# mbed-WiFi-BLE-Cloud-v1_2_0.net
KiCad netlist of a schematic drawn in EAGLE
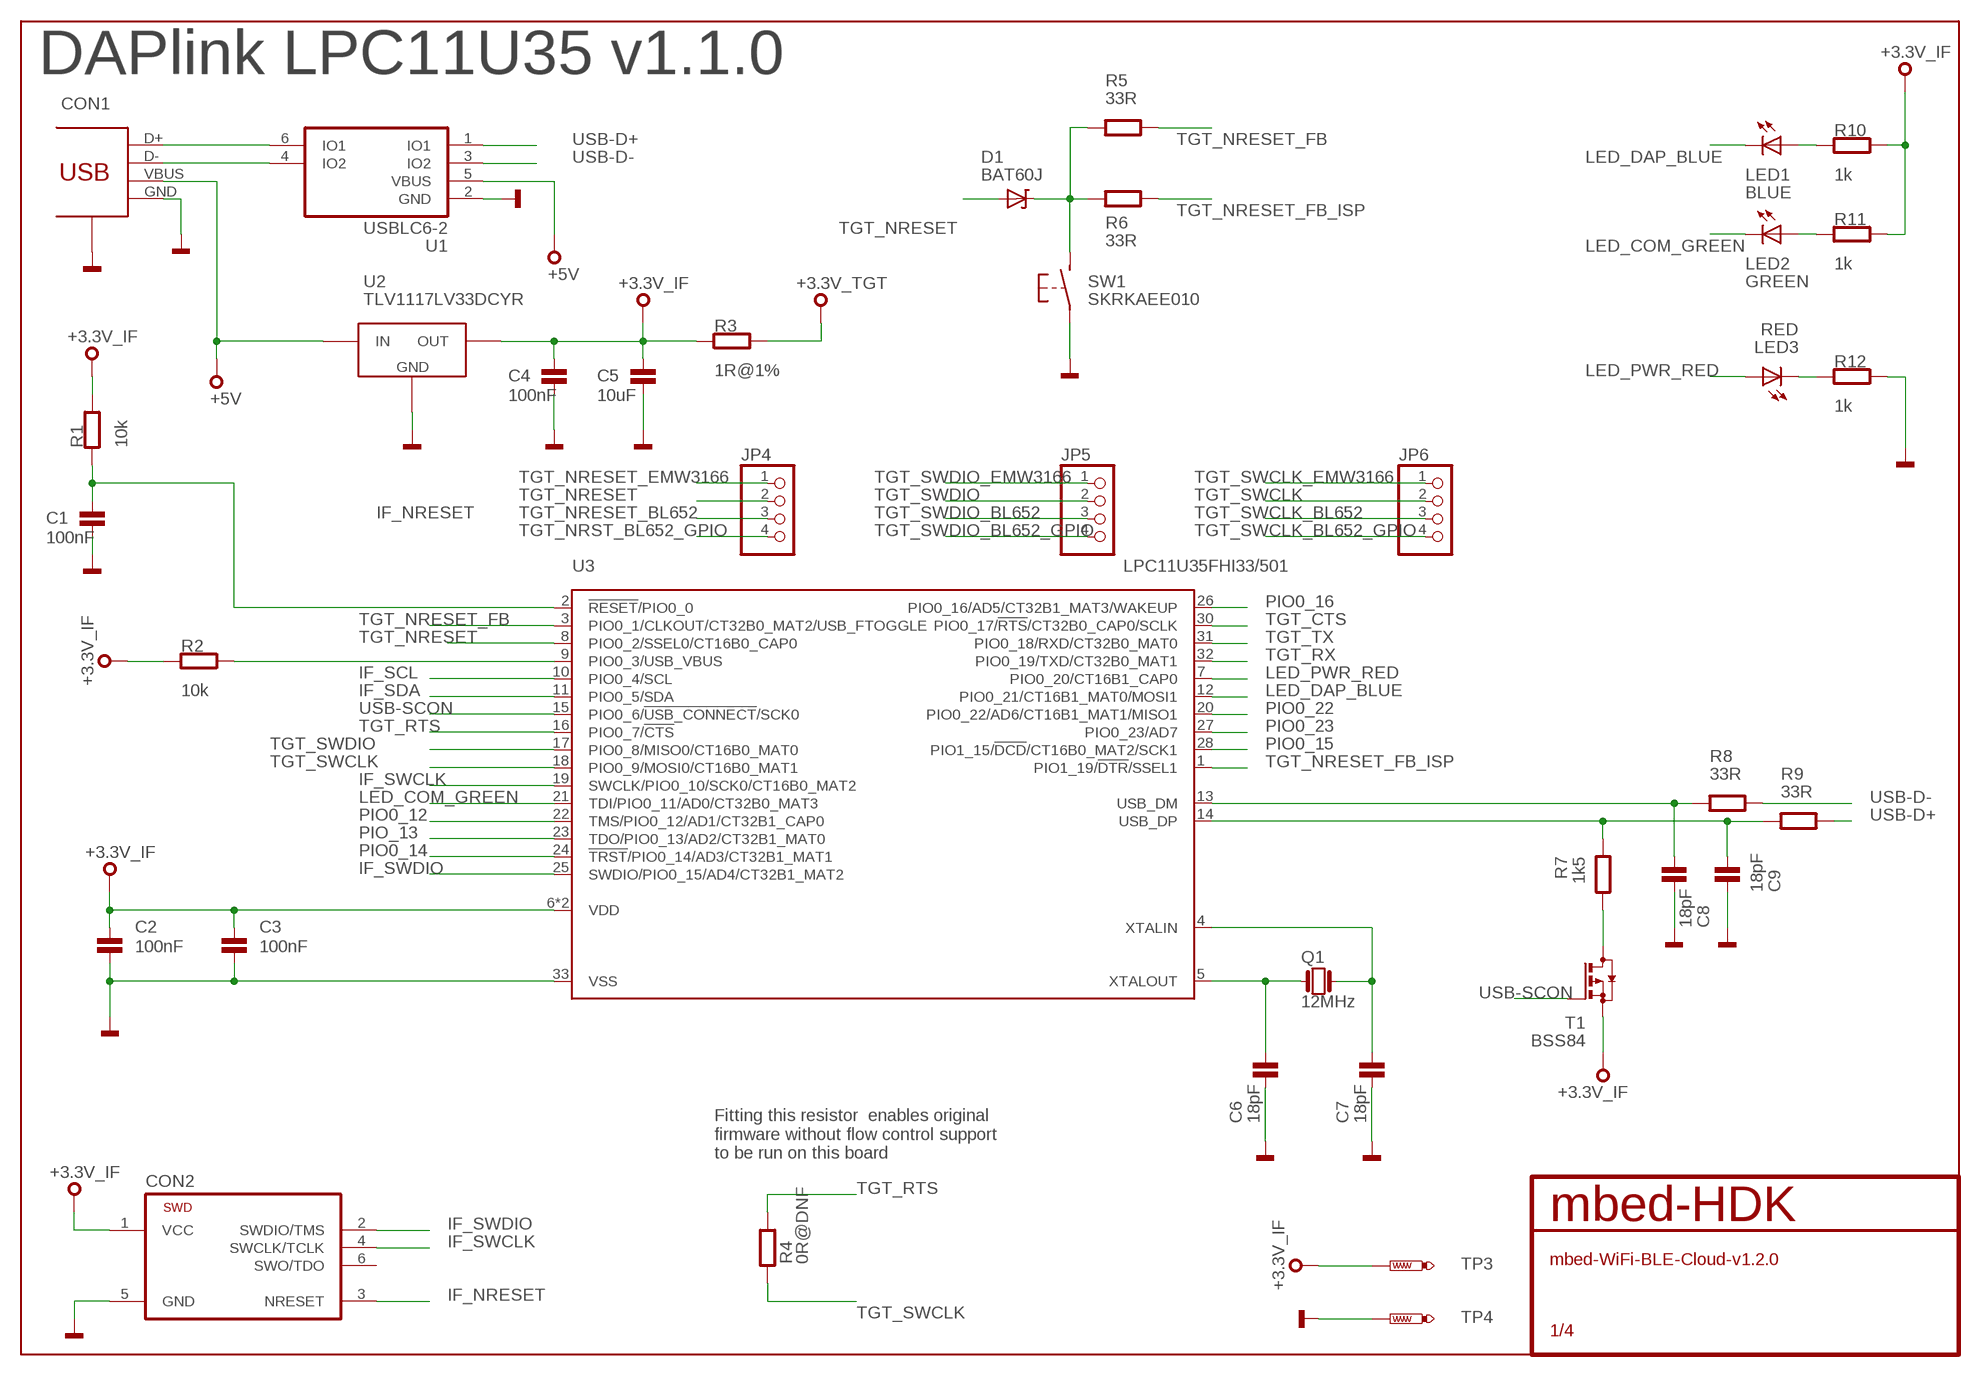
[diagram p0: schematic, sheet 1]
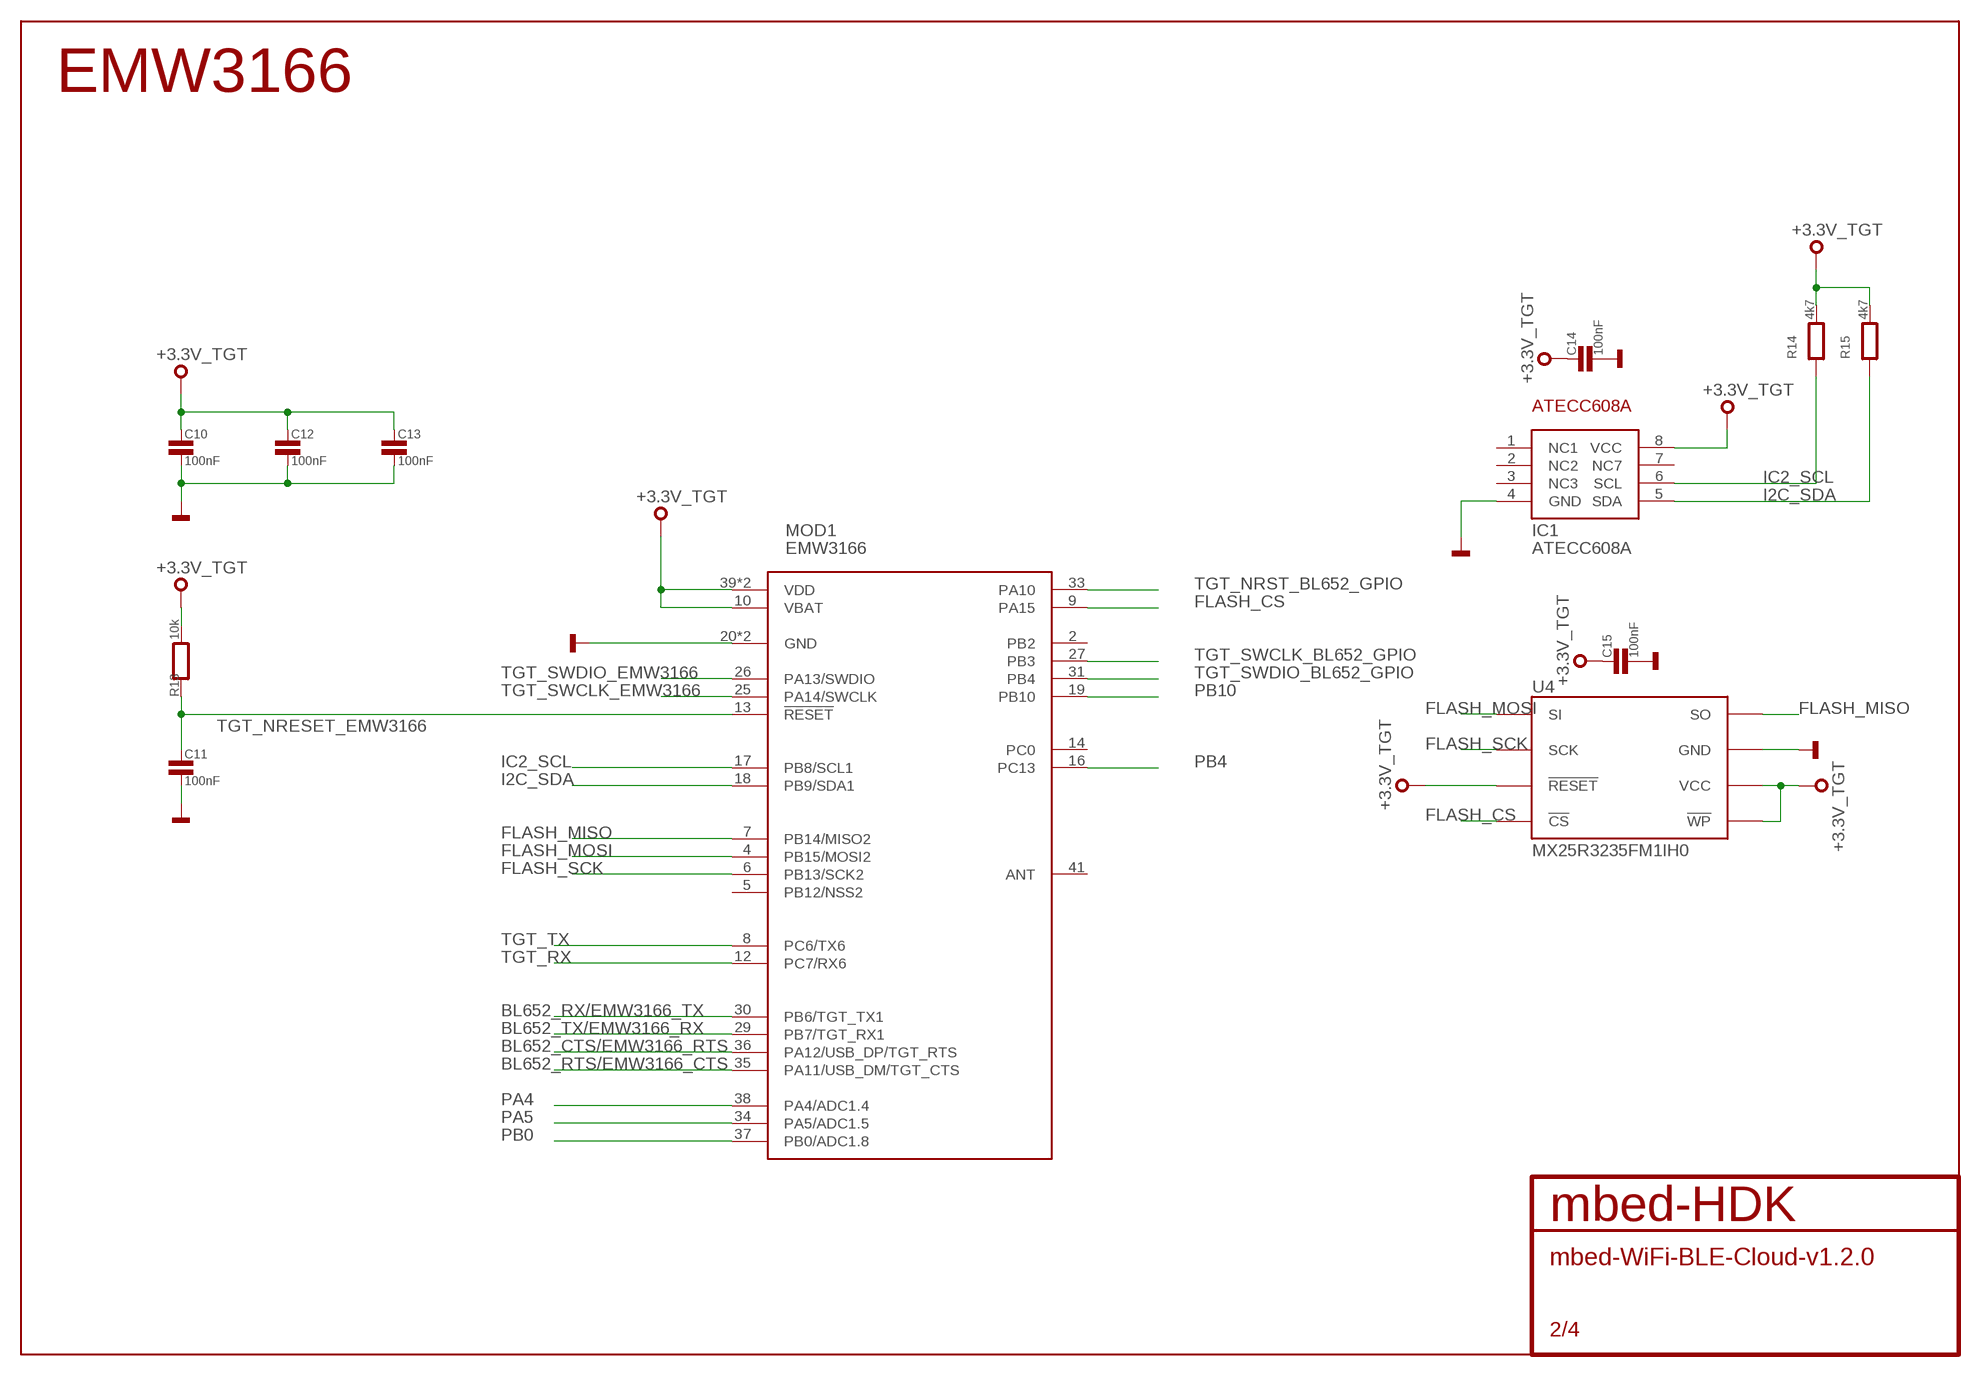
[diagram p1: schematic, sheet 2]
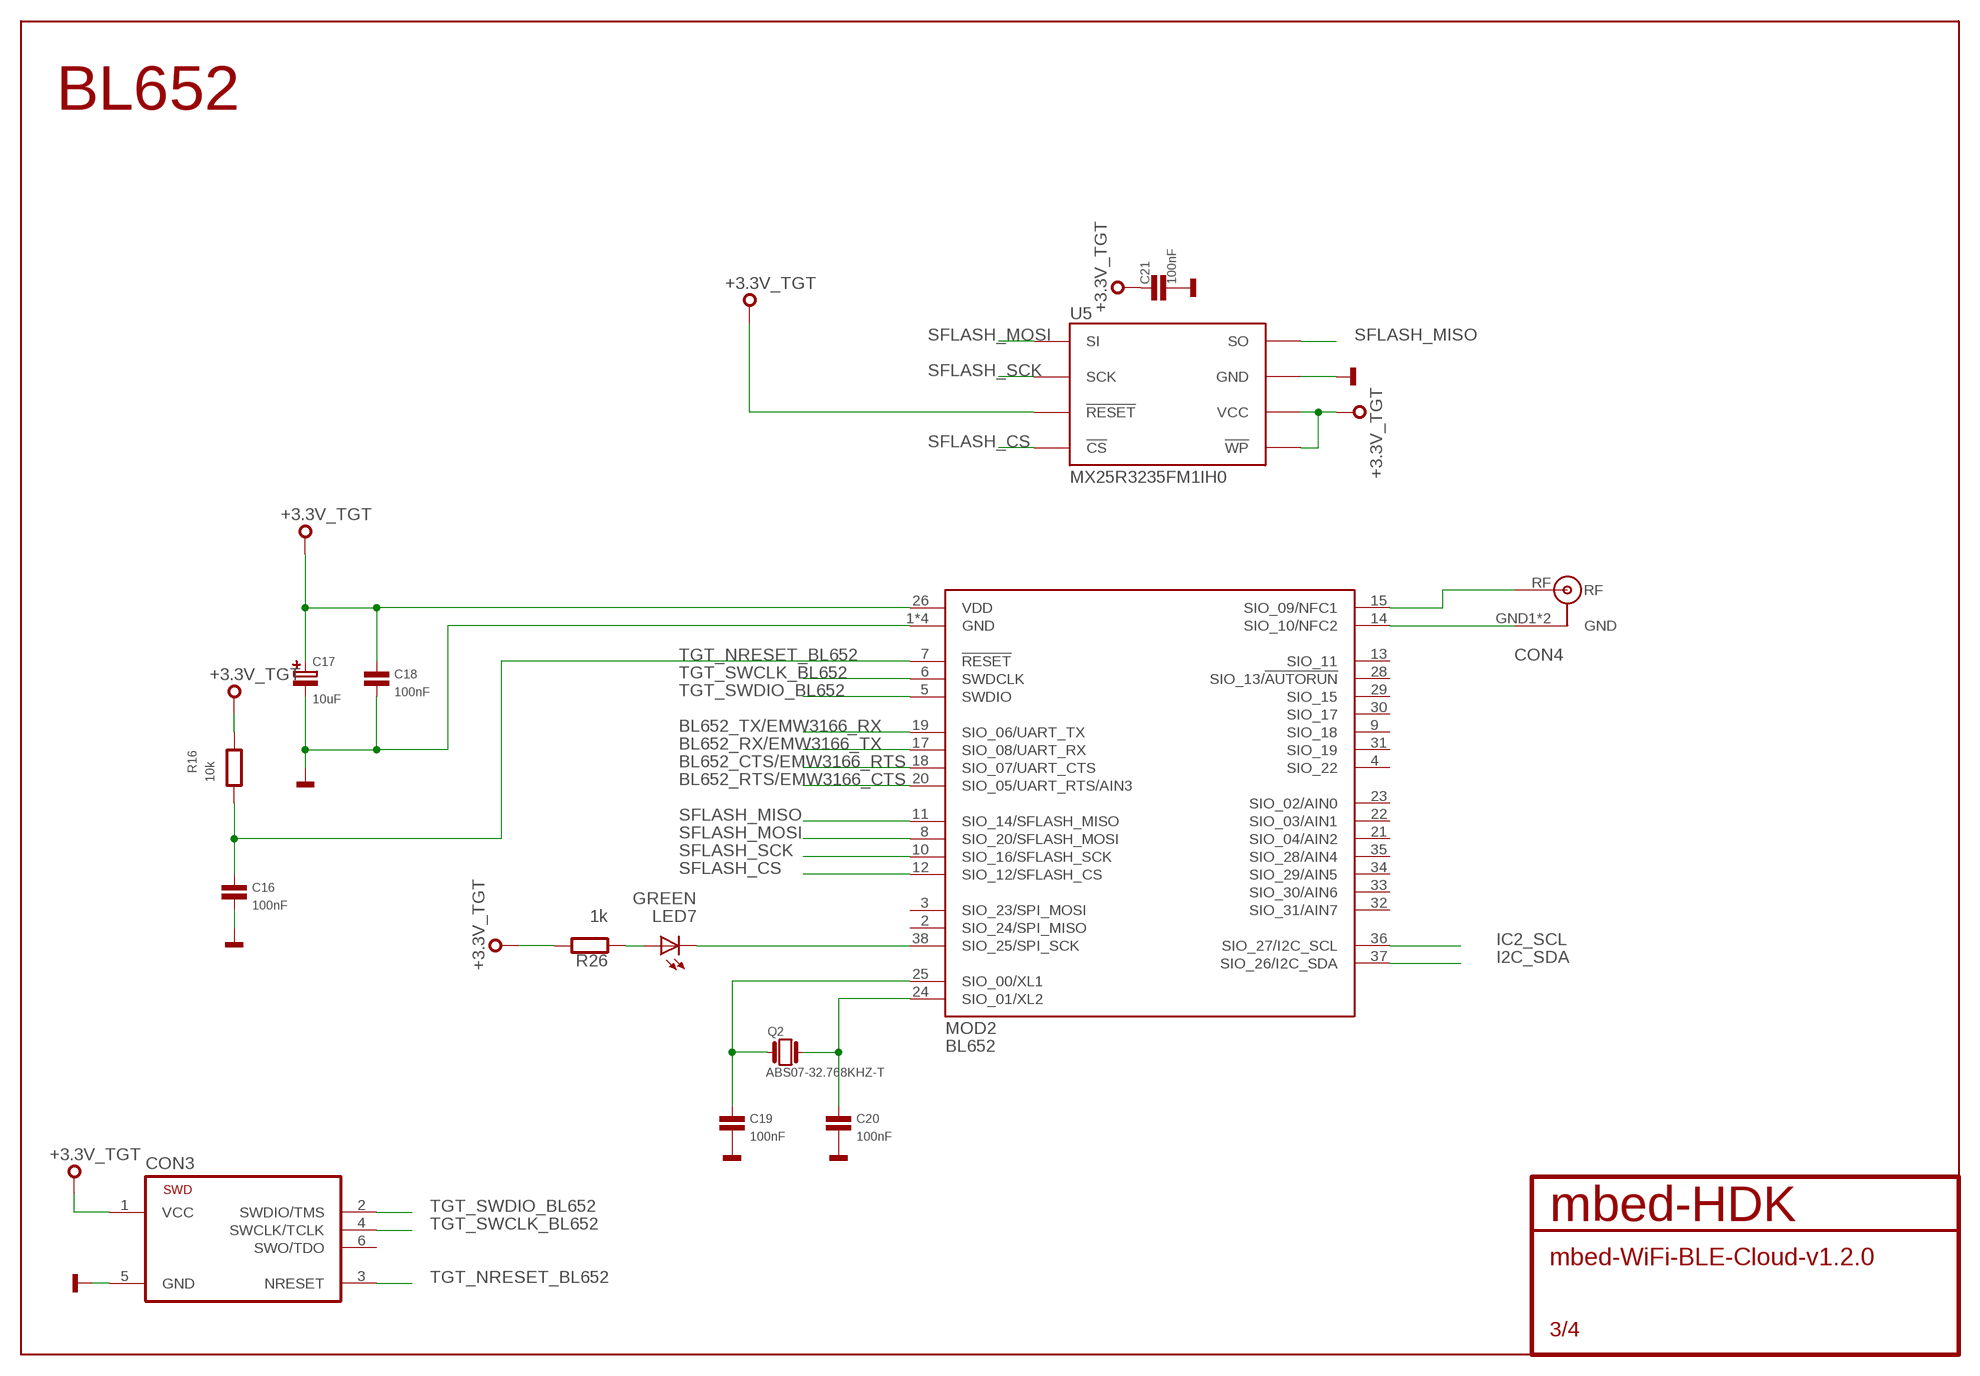
[diagram p2: schematic, sheet 3]
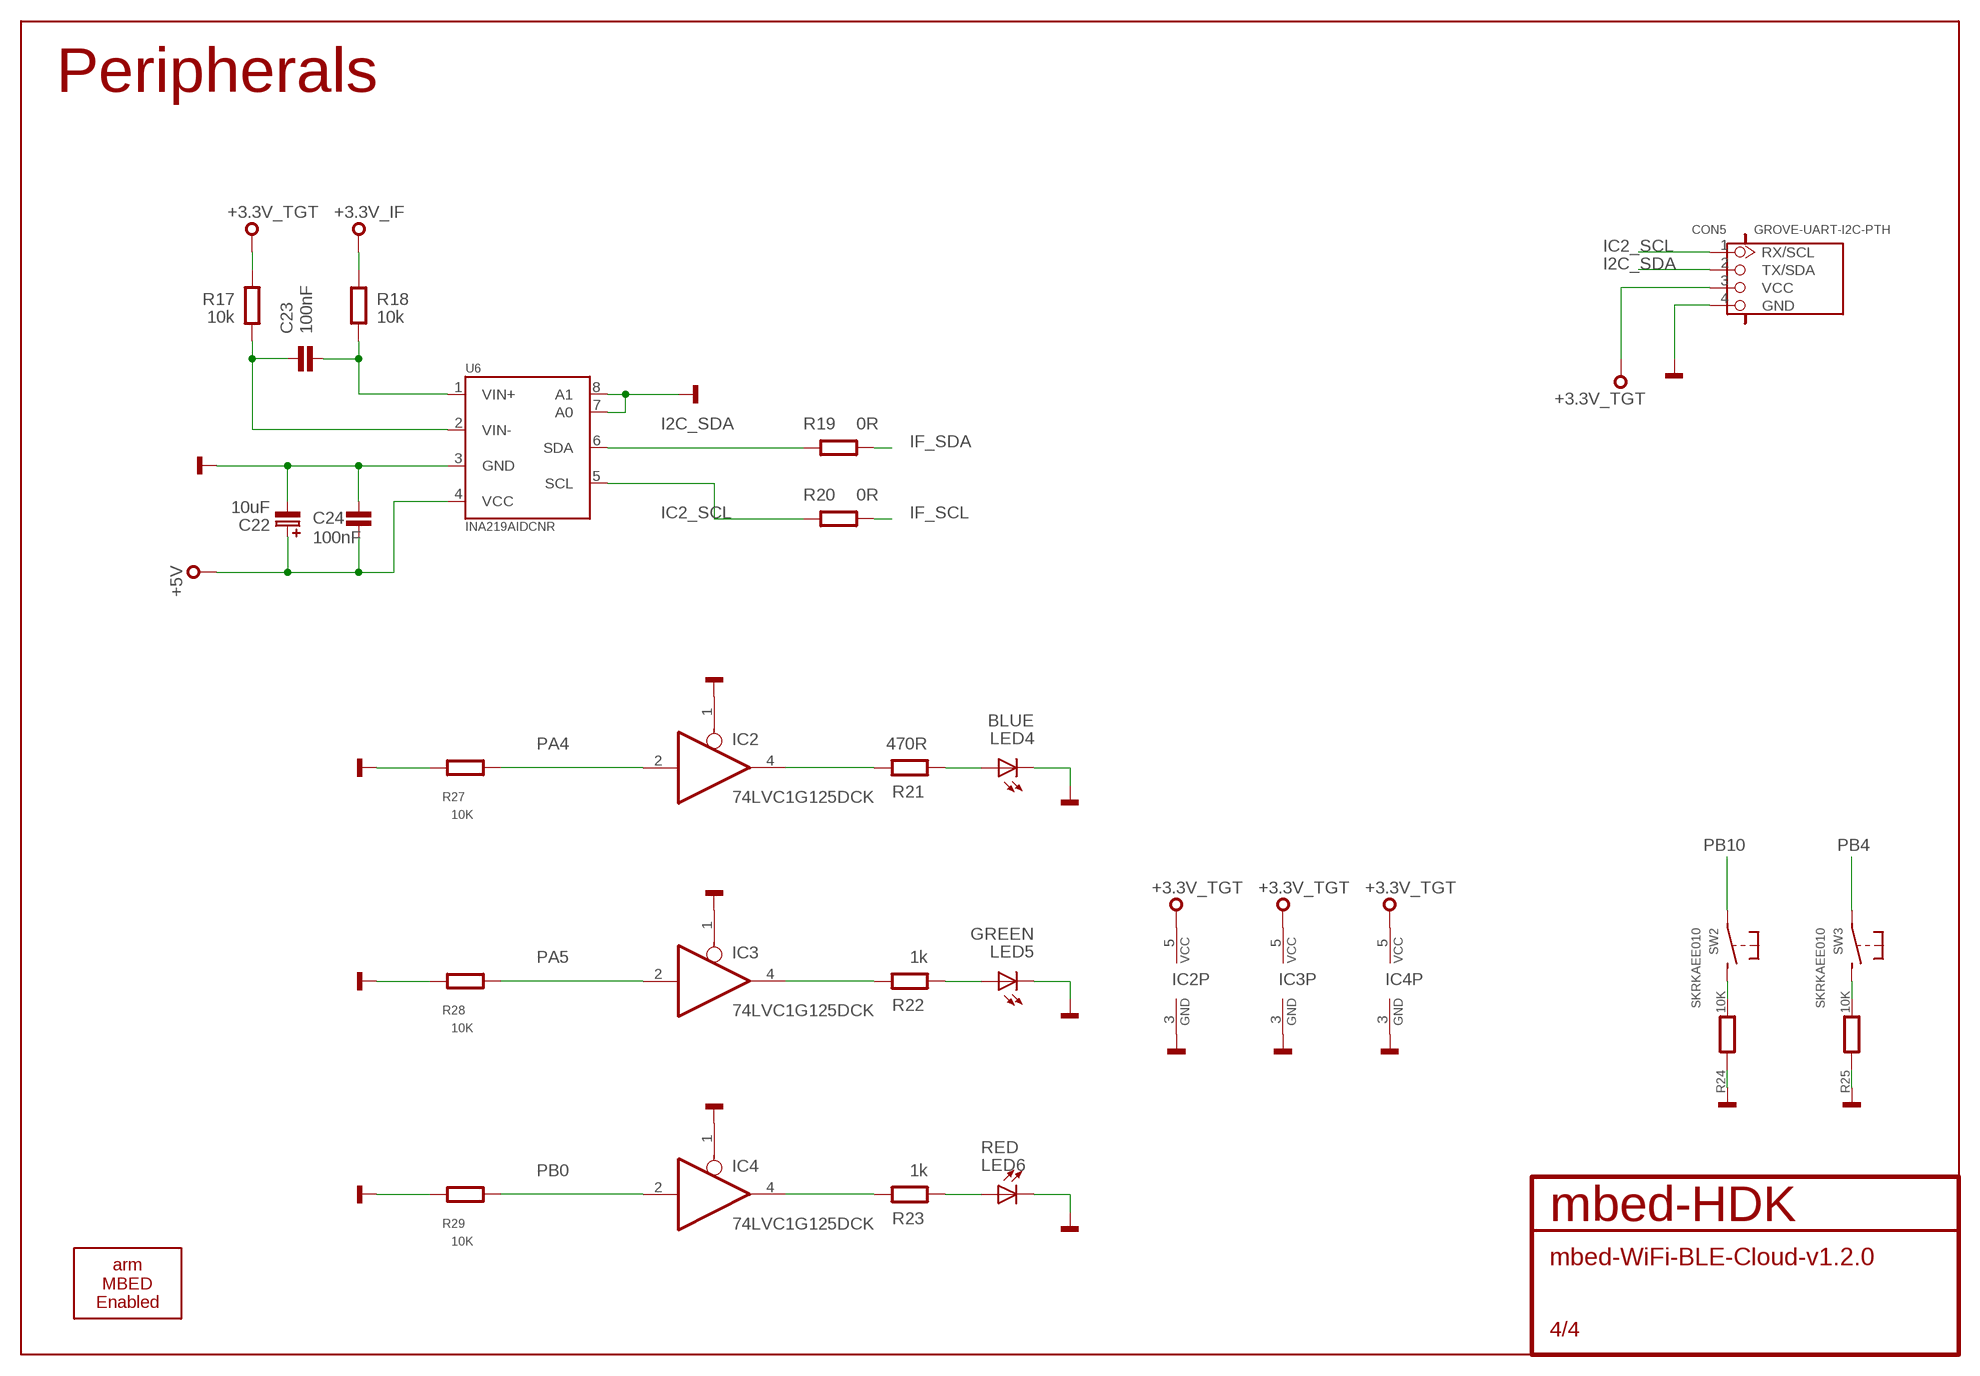
[diagram p3: schematic, sheet 4]

(export (version "E")
  (design (tool "Eeschema 10.0.6"))
  (components
    (comp (ref "C10")
      (value "100nF")
      (footprint "eagle-import:0603")
      (libsource (lib "eagle-import") (part "mbed-HDK-RLC_C0603"))
    )
    (comp (ref "C11")
      (value "100nF")
      (footprint "eagle-import:0603")
      (libsource (lib "eagle-import") (part "mbed-HDK-RLC_C0603"))
    )
    (comp (ref "C12")
      (value "100nF")
      (footprint "eagle-import:0603")
      (libsource (lib "eagle-import") (part "mbed-HDK-RLC_C0603"))
    )
    (comp (ref "C13")
      (value "100nF")
      (footprint "eagle-import:0603")
      (libsource (lib "eagle-import") (part "mbed-HDK-RLC_C0603"))
    )
    (comp (ref "C14")
      (value "100nF")
      (footprint "eagle-import:0603")
      (libsource (lib "eagle-import") (part "mbed-HDK-RLC_C0603"))
    )
    (comp (ref "C15")
      (value "100nF")
      (footprint "eagle-import:0603")
      (libsource (lib "eagle-import") (part "mbed-HDK-RLC_C0603"))
    )
    (comp (ref "IC1")
      (value "ATECC608A")
      (footprint "eagle-import:SO8")
      (libsource (lib "eagle-import") (part "ATECC608A"))
    )
    (comp (ref "MOD1")
      (value "EMW3166")
      (footprint "eagle-import:EMW3166")
      (libsource (lib "eagle-import") (part "EMW3166"))
    )
    (comp (ref "R13")
      (value "10k")
      (footprint "eagle-import:0603")
      (libsource (lib "eagle-import") (part "R0603"))
    )
    (comp (ref "R14")
      (value "4k7")
      (footprint "eagle-import:0603")
      (libsource (lib "eagle-import") (part "R0603"))
    )
    (comp (ref "R15")
      (value "4k7")
      (footprint "eagle-import:0603")
      (libsource (lib "eagle-import") (part "R0603"))
    )
    (comp (ref "U4")
      (value "MX25R3235FM1IH0")
      (footprint "eagle-import:SO8")
      (fields (field (name "MF") "Macronix"))
      (libsource (lib "eagle-import") (part "MX25R3235FM1IH0"))
    )
    (comp (ref "C16")
      (value "100nF")
      (footprint "eagle-import:0603")
      (libsource (lib "eagle-import") (part "C0603"))
    )
    (comp (ref "C17")
      (value "10uF")
      (footprint "eagle-import:SMC_B")
      (fields (field (name "MF") "Kemet"))
      (libsource (lib "eagle-import") (part "C-POLB"))
    )
    (comp (ref "C18")
      (value "100nF")
      (footprint "eagle-import:0603")
      (libsource (lib "eagle-import") (part "C0603"))
    )
    (comp (ref "C19")
      (value "100nF")
      (footprint "eagle-import:0603")
      (libsource (lib "eagle-import") (part "C0603"))
    )
    (comp (ref "C20")
      (value "100nF")
      (footprint "eagle-import:0603")
      (libsource (lib "eagle-import") (part "C0603"))
    )
    (comp (ref "C21")
      (value "100nF")
      (footprint "eagle-import:0603")
      (libsource (lib "eagle-import") (part "mbed-HDK-RLC_C0603"))
    )
    (comp (ref "CON3")
      (value "TC2030-CTX-NL")
      (footprint "eagle-import:TC2030-CTX-NL")
      (libsource (lib "eagle-import") (part "TC2030-CTX-NL"))
    )
    (comp (ref "CON4")
      (value "U.FL")
      (footprint "eagle-import:U.FL-R-SMT-1")
      (fields (field (name "MF") "Hirose"))
      (libsource (lib "eagle-import") (part "U.FL"))
    )
    (comp (ref "LED7")
      (value "GREEN")
      (footprint "eagle-import:CHIPLED_0603")
      (libsource (lib "eagle-import") (part "mbed-HDK-Optical_LED0603"))
    )
    (comp (ref "MOD2")
      (value "BL652")
      (footprint "eagle-import:BL652")
      (libsource (lib "eagle-import") (part "BL652"))
    )
    (comp (ref "Q2")
      (value "ABS07-32.768KHZ-T")
      (footprint "eagle-import:FC135")
      (fields (field (name "MF") "Abracon"))
      (libsource (lib "eagle-import") (part "ABS07-32.768KHZ-T"))
    )
    (comp (ref "R16")
      (value "10k")
      (footprint "eagle-import:0603")
      (libsource (lib "eagle-import") (part "R0603"))
    )
    (comp (ref "R26")
      (value "1k")
      (footprint "eagle-import:0603")
      (libsource (lib "eagle-import") (part "R0603"))
    )
    (comp (ref "U5")
      (value "MX25R3235FM1IH0")
      (footprint "eagle-import:SO8")
      (fields (field (name "MF") "Macronix"))
      (libsource (lib "eagle-import") (part "MX25R3235FM1IH0"))
    )
    (comp (ref "C1")
      (value "100nF")
      (footprint "eagle-import:0603")
      (libsource (lib "eagle-import") (part "mbed-HDK-RLC_C0603"))
    )
    (comp (ref "C2")
      (value "100nF")
      (footprint "eagle-import:0603")
      (libsource (lib "eagle-import") (part "mbed-HDK-RLC_C0603"))
    )
    (comp (ref "C3")
      (value "100nF")
      (footprint "eagle-import:0603")
      (libsource (lib "eagle-import") (part "mbed-HDK-RLC_C0603"))
    )
    (comp (ref "C4")
      (value "100nF")
      (footprint "eagle-import:0603")
      (libsource (lib "eagle-import") (part "mbed-HDK-RLC_C0603"))
    )
    (comp (ref "C5")
      (value "10uF")
      (footprint "eagle-import:0603")
      (libsource (lib "eagle-import") (part "mbed-HDK-RLC_C0603"))
    )
    (comp (ref "C6")
      (value "18pF")
      (footprint "eagle-import:0603")
      (libsource (lib "eagle-import") (part "mbed-HDK-RLC_C0603"))
    )
    (comp (ref "C7")
      (value "18pF")
      (footprint "eagle-import:0603")
      (libsource (lib "eagle-import") (part "mbed-HDK-RLC_C0603"))
    )
    (comp (ref "C8")
      (value "18pF")
      (footprint "eagle-import:0603")
      (libsource (lib "eagle-import") (part "mbed-HDK-RLC_C0603"))
    )
    (comp (ref "C9")
      (value "18pF")
      (footprint "eagle-import:0603")
      (libsource (lib "eagle-import") (part "mbed-HDK-RLC_C0603"))
    )
    (comp (ref "CON1")
      (value "47346-0001")
      (footprint "eagle-import:USB-MICRO-B-H")
      (fields (field (name "MF") "MOLEX"))
      (libsource (lib "eagle-import") (part "47346-0001"))
    )
    (comp (ref "CON2")
      (value "TC2030-CTX-NL")
      (footprint "eagle-import:TC2030-CTX-NL")
      (libsource (lib "eagle-import") (part "TC2030-CTX-NL"))
    )
    (comp (ref "D1")
      (value "BAT60J")
      (footprint "eagle-import:SOD323")
      (fields (field (name "MF") "STMicroelectronics"))
      (libsource (lib "eagle-import") (part "BAT60J"))
    )
    (comp (ref "JP4")
      (value "PINHD-1X4")
      (footprint "eagle-import:1X04")
      (libsource (lib "eagle-import") (part "PINHD-1X4"))
    )
    (comp (ref "JP5")
      (value "PINHD-1X4")
      (footprint "eagle-import:1X04")
      (libsource (lib "eagle-import") (part "PINHD-1X4"))
    )
    (comp (ref "JP6")
      (value "PINHD-1X4")
      (footprint "eagle-import:1X04")
      (libsource (lib "eagle-import") (part "PINHD-1X4"))
    )
    (comp (ref "LED1")
      (value "BLUE")
      (footprint "eagle-import:CHIPLED_0603")
      (libsource (lib "eagle-import") (part "mbed-HDK-Optical_LED0603"))
    )
    (comp (ref "LED2")
      (value "GREEN")
      (footprint "eagle-import:CHIPLED_0603")
      (libsource (lib "eagle-import") (part "mbed-HDK-Optical_LED0603"))
    )
    (comp (ref "LED3")
      (value "RED")
      (footprint "eagle-import:CHIPLED_0603")
      (libsource (lib "eagle-import") (part "mbed-HDK-Optical_LED0603"))
    )
    (comp (ref "Q1")
      (value "12MHz")
      (footprint "eagle-import:3.2X2.5")
      (libsource (lib "eagle-import") (part "Q_3.2X2.5"))
    )
    (comp (ref "R1")
      (value "10k")
      (footprint "eagle-import:0603")
      (libsource (lib "eagle-import") (part "R0603"))
    )
    (comp (ref "R2")
      (value "10k")
      (footprint "eagle-import:0603")
      (libsource (lib "eagle-import") (part "R0603"))
    )
    (comp (ref "R3")
      (value "1R@1%")
      (footprint "eagle-import:0603")
      (libsource (lib "eagle-import") (part "R0603"))
    )
    (comp (ref "R4")
      (value "0R@DNF")
      (footprint "eagle-import:0603")
      (libsource (lib "eagle-import") (part "R0603"))
    )
    (comp (ref "R5")
      (value "33R")
      (footprint "eagle-import:0603")
      (libsource (lib "eagle-import") (part "R0603"))
    )
    (comp (ref "R6")
      (value "33R")
      (footprint "eagle-import:0603")
      (libsource (lib "eagle-import") (part "R0603"))
    )
    (comp (ref "R7")
      (value "1k5")
      (footprint "eagle-import:0603")
      (libsource (lib "eagle-import") (part "R0603"))
    )
    (comp (ref "R8")
      (value "33R")
      (footprint "eagle-import:0603")
      (libsource (lib "eagle-import") (part "R0603"))
    )
    (comp (ref "R9")
      (value "33R")
      (footprint "eagle-import:0603")
      (libsource (lib "eagle-import") (part "R0603"))
    )
    (comp (ref "R10")
      (value "1k")
      (footprint "eagle-import:0603")
      (libsource (lib "eagle-import") (part "R0603"))
    )
    (comp (ref "R11")
      (value "1k")
      (footprint "eagle-import:0603")
      (libsource (lib "eagle-import") (part "R0603"))
    )
    (comp (ref "R12")
      (value "1k")
      (footprint "eagle-import:0603")
      (libsource (lib "eagle-import") (part "R0603"))
    )
    (comp (ref "SW1")
      (value "SKRKAEE010")
      (footprint "eagle-import:SKRKAEE010")
      (fields (field (name "MF") "ALPS"))
      (libsource (lib "eagle-import") (part "SKRKAEE010"))
    )
    (comp (ref "T1")
      (value "BSS84")
      (footprint "eagle-import:SOT23-3")
      (fields (field (name "MF") "Fairchild Semiconductor"))
      (libsource (lib "eagle-import") (part "BSS84"))
    )
    (comp (ref "TP3")
      (value "PTR1PAD1-13")
      (footprint "eagle-import:P1-13")
      (libsource (lib "eagle-import") (part "PTR1PAD1-13"))
    )
    (comp (ref "TP4")
      (value "PTR1PAD1-13")
      (footprint "eagle-import:P1-13")
      (libsource (lib "eagle-import") (part "PTR1PAD1-13"))
    )
    (comp (ref "U1")
      (value "USBLC6-2SC6")
      (footprint "eagle-import:SOT23-6L")
      (fields (field (name "MF") "STMicro"))
      (libsource (lib "eagle-import") (part "USBLC6-2SC6"))
    )
    (comp (ref "U2")
      (value "TLV1117LV33DCYR")
      (footprint "eagle-import:SOT223")
      (fields (field (name "MF") "Texas Instruments"))
      (libsource (lib "eagle-import") (part "TLV1117LV33DCYR"))
    )
    (comp (ref "U3")
      (value "LPC11U35FHI33/501")
      (footprint "eagle-import:SOT617-3")
      (fields (field (name "MF") "NXP"))
      (libsource (lib "eagle-import") (part "LPC11U35FHI33/501"))
    )
    (comp (ref "C22")
      (value "10uF")
      (footprint "eagle-import:SMC_B")
      (fields (field (name "MF") "Kemet"))
      (libsource (lib "eagle-import") (part "C-POLB"))
    )
    (comp (ref "C23")
      (value "100nF")
      (footprint "eagle-import:0603")
      (libsource (lib "eagle-import") (part "C0603"))
    )
    (comp (ref "C24")
      (value "100nF")
      (footprint "eagle-import:0603")
      (libsource (lib "eagle-import") (part "C0603"))
    )
    (comp (ref "CON5")
      (value "GROVE-UART-I2C-PTH")
      (footprint "eagle-import:HW4-2.0")
      (libsource (lib "eagle-import") (part "GROVE-UART-I2C-PTH"))
    )
    (comp (ref "IC2")
      (value "74LVC1G125DCK")
      (footprint "eagle-import:SC70-5")
      (libsource (lib "eagle-import") (part "741G125DCKLVC"))
    )
    (comp (ref "IC3")
      (value "74LVC1G125DCK")
      (footprint "eagle-import:SC70-5")
      (libsource (lib "eagle-import") (part "741G125DCKLVC"))
    )
    (comp (ref "IC4")
      (value "74LVC1G125DCK")
      (footprint "eagle-import:SC70-5")
      (libsource (lib "eagle-import") (part "741G125DCKLVC"))
    )
    (comp (ref "LED4")
      (value "BLUE")
      (footprint "eagle-import:CHIPLED_0603")
      (libsource (lib "eagle-import") (part "LED0603"))
    )
    (comp (ref "LED5")
      (value "GREEN")
      (footprint "eagle-import:CHIPLED_0603")
      (libsource (lib "eagle-import") (part "LED0603"))
    )
    (comp (ref "LED6")
      (value "RED")
      (footprint "eagle-import:CHIPLED_0603")
      (libsource (lib "eagle-import") (part "LED0603"))
    )
    (comp (ref "R17")
      (value "10k")
      (footprint "eagle-import:0603")
      (libsource (lib "eagle-import") (part "R0603"))
    )
    (comp (ref "R18")
      (value "10k")
      (footprint "eagle-import:0603")
      (libsource (lib "eagle-import") (part "R0603"))
    )
    (comp (ref "R19")
      (value "0R")
      (footprint "eagle-import:0603")
      (libsource (lib "eagle-import") (part "R0603"))
    )
    (comp (ref "R20")
      (value "0R")
      (footprint "eagle-import:0603")
      (libsource (lib "eagle-import") (part "R0603"))
    )
    (comp (ref "R21")
      (value "470R")
      (footprint "eagle-import:0603")
      (libsource (lib "eagle-import") (part "R0603"))
    )
    (comp (ref "R22")
      (value "1k")
      (footprint "eagle-import:0603")
      (libsource (lib "eagle-import") (part "R0603"))
    )
    (comp (ref "R23")
      (value "1k")
      (footprint "eagle-import:0603")
      (libsource (lib "eagle-import") (part "R0603"))
    )
    (comp (ref "R24")
      (value "10K")
      (footprint "eagle-import:0603")
      (libsource (lib "eagle-import") (part "R0603"))
    )
    (comp (ref "R25")
      (value "10K")
      (footprint "eagle-import:0603")
      (libsource (lib "eagle-import") (part "R0603"))
    )
    (comp (ref "R27")
      (value "10K")
      (footprint "eagle-import:0603")
      (libsource (lib "eagle-import") (part "R0603"))
    )
    (comp (ref "R28")
      (value "10K")
      (footprint "eagle-import:0603")
      (libsource (lib "eagle-import") (part "R0603"))
    )
    (comp (ref "R29")
      (value "10K")
      (footprint "eagle-import:0603")
      (libsource (lib "eagle-import") (part "R0603"))
    )
    (comp (ref "SS1")
      (value "ARM-MBED-ENABLED-12MM")
      (footprint "eagle-import:ARM-MBED-ENABLED-12MM")
      (libsource (lib "eagle-import") (part "ARM-MBED-ENABLED-12MM"))
    )
    (comp (ref "SW2")
      (value "SKRKAEE010")
      (footprint "eagle-import:SKRKAEE010")
      (fields (field (name "MF") "ALPS"))
      (libsource (lib "eagle-import") (part "SKRKAEE010"))
    )
    (comp (ref "SW3")
      (value "SKRKAEE010")
      (footprint "eagle-import:SKRKAEE010")
      (fields (field (name "MF") "ALPS"))
      (libsource (lib "eagle-import") (part "SKRKAEE010"))
    )
    (comp (ref "U6")
      (value "INA219AIDCNR")
      (footprint "eagle-import:SOT23-8")
      (fields (field (name "MF") "Texas Instruments"))
      (libsource (lib "eagle-import") (part "INA219AIDCNR"))
    )
  )
  (nets
    (net (code "1") (name "+3.3V_IF") (class "Default")
      (node (ref "C2") (pin "1") (pinfunction "P$1_1") (pintype "passive"))
      (node (ref "C3") (pin "1") (pinfunction "P$1_1") (pintype "passive"))
      (node (ref "C4") (pin "1") (pinfunction "P$1_1") (pintype "passive"))
      (node (ref "C5") (pin "1") (pinfunction "P$1_1") (pintype "passive"))
      (node (ref "CON2") (pin "1") (pinfunction "VCC_1") (pintype "passive"))
      (node (ref "R1") (pin "2") (pinfunction "P$2_2") (pintype "passive"))
      (node (ref "R10") (pin "2") (pinfunction "P$2_2") (pintype "passive"))
      (node (ref "R11") (pin "2") (pinfunction "P$2_2") (pintype "passive"))
      (node (ref "R18") (pin "2") (pinfunction "P$2_2") (pintype "passive"))
      (node (ref "R2") (pin "1") (pinfunction "P$1_1") (pintype "passive"))
      (node (ref "R3") (pin "1") (pinfunction "P$1_1") (pintype "passive"))
      (node (ref "T1") (pin "2") (pinfunction "S_2") (pintype "passive"))
      (node (ref "TP3") (pin "TP") (pinfunction "TP_TP") (pintype "input"))
      (node (ref "U2") (pin "2") (pinfunction "OUT_2") (pintype "bidirectional"))
      (node (ref "U2") (pin "4") (pinfunction "OUT_4") (pintype "bidirectional"))
      (node (ref "U3") (pin "29") (pinfunction "VDD_29") (pintype "passive"))
      (node (ref "U3") (pin "6") (pinfunction "VDD_6") (pintype "passive"))
    )
    (net (code "2") (name "+3.3V_TGT") (class "Default")
      (node (ref "C10") (pin "1") (pinfunction "P$1_1") (pintype "passive"))
      (node (ref "C12") (pin "1") (pinfunction "P$1_1") (pintype "passive"))
      (node (ref "C13") (pin "1") (pinfunction "P$1_1") (pintype "passive"))
      (node (ref "C14") (pin "1") (pinfunction "P$1_1") (pintype "passive"))
      (node (ref "C15") (pin "1") (pinfunction "P$1_1") (pintype "passive"))
      (node (ref "C17") (pin "+") (pinfunction "+_+") (pintype "passive"))
      (node (ref "C18") (pin "1") (pinfunction "P$1_1") (pintype "passive"))
      (node (ref "C21") (pin "1") (pinfunction "P$1_1") (pintype "passive"))
      (node (ref "CON3") (pin "1") (pinfunction "VCC_1") (pintype "passive"))
      (node (ref "CON5") (pin "3") (pinfunction "VCC_3") (pintype "bidirectional"))
      (node (ref "IC1") (pin "8") (pinfunction "VCC_8") (pintype "bidirectional"))
      (node (ref "IC2") (pin "5") (pinfunction "VCC_5") (pintype "power_in"))
      (node (ref "IC3") (pin "5") (pinfunction "VCC_5") (pintype "power_in"))
      (node (ref "IC4") (pin "5") (pinfunction "VCC_5") (pintype "power_in"))
      (node (ref "MOD1") (pin "10") (pinfunction "VBAT_10") (pintype "bidirectional"))
      (node (ref "MOD1") (pin "39") (pinfunction "VDD_39") (pintype "bidirectional"))
      (node (ref "MOD1") (pin "40") (pinfunction "VDD_40") (pintype "bidirectional"))
      (node (ref "MOD2") (pin "26") (pinfunction "VDD_26") (pintype "bidirectional"))
      (node (ref "R13") (pin "2") (pinfunction "P$2_2") (pintype "passive"))
      (node (ref "R14") (pin "2") (pinfunction "P$2_2") (pintype "passive"))
      (node (ref "R15") (pin "2") (pinfunction "P$2_2") (pintype "passive"))
      (node (ref "R16") (pin "2") (pinfunction "P$2_2") (pintype "passive"))
      (node (ref "R17") (pin "2") (pinfunction "P$2_2") (pintype "passive"))
      (node (ref "R26") (pin "2") (pinfunction "P$2_2") (pintype "passive"))
      (node (ref "R3") (pin "2") (pinfunction "P$2_2") (pintype "passive"))
      (node (ref "U4") (pin "3") (pinfunction "~{WP}_3") (pintype "bidirectional"))
      (node (ref "U4") (pin "7") (pinfunction "~{RESET}_7") (pintype "bidirectional"))
      (node (ref "U4") (pin "8") (pinfunction "VCC_8") (pintype "bidirectional"))
      (node (ref "U5") (pin "3") (pinfunction "~{WP}_3") (pintype "bidirectional"))
      (node (ref "U5") (pin "7") (pinfunction "~{RESET}_7") (pintype "bidirectional"))
      (node (ref "U5") (pin "8") (pinfunction "VCC_8") (pintype "bidirectional"))
    )
    (net (code "3") (name "+5V") (class "Default")
      (node (ref "C22") (pin "+") (pinfunction "+_+") (pintype "passive"))
      (node (ref "C24") (pin "2") (pinfunction "P$2_2") (pintype "passive"))
      (node (ref "CON1") (pin "VBUS") (pinfunction "VBUS_VBUS") (pintype "bidirectional"))
      (node (ref "U1") (pin "5") (pinfunction "VBUS_5") (pintype "bidirectional"))
      (node (ref "U2") (pin "3") (pinfunction "IN_3") (pintype "bidirectional"))
      (node (ref "U6") (pin "4") (pinfunction "VCC_4") (pintype "power_in"))
    )
    (net (code "4") (name "BL652_CTS{slash}EMW3166_RTS") (class "Default")
      (node (ref "MOD1") (pin "36") (pinfunction "PA12/USB_DP/TGT_RTS_36") (pintype "bidirectional"))
      (node (ref "MOD2") (pin "18") (pinfunction "SIO_07/UART_CTS_18") (pintype "bidirectional"))
    )
    (net (code "5") (name "BL652_RTS{slash}EMW3166_CTS") (class "Default")
      (node (ref "MOD1") (pin "35") (pinfunction "PA11/USB_DM/TGT_CTS_35") (pintype "bidirectional"))
      (node (ref "MOD2") (pin "20") (pinfunction "SIO_05/UART_RTS/AIN3_20") (pintype "bidirectional"))
    )
    (net (code "6") (name "BL652_RX{slash}EMW3166_TX") (class "Default")
      (node (ref "MOD1") (pin "30") (pinfunction "PB6/TGT_TX1_30") (pintype "bidirectional"))
      (node (ref "MOD2") (pin "17") (pinfunction "SIO_08/UART_RX_17") (pintype "bidirectional"))
    )
    (net (code "7") (name "BL652_TX{slash}EMW3166_RX") (class "Default")
      (node (ref "MOD1") (pin "29") (pinfunction "PB7/TGT_RX1_29") (pintype "bidirectional"))
      (node (ref "MOD2") (pin "19") (pinfunction "SIO_06/UART_TX_19") (pintype "bidirectional"))
    )
    (net (code "8") (name "FLASH_CS") (class "Default")
      (node (ref "MOD1") (pin "9") (pinfunction "PA15_9") (pintype "bidirectional"))
      (node (ref "U4") (pin "1") (pinfunction "~{CS}_1") (pintype "bidirectional"))
    )
    (net (code "9") (name "FLASH_MISO") (class "Default")
      (node (ref "MOD1") (pin "7") (pinfunction "PB14/MISO2_7") (pintype "bidirectional"))
      (node (ref "U4") (pin "2") (pinfunction "SO_2") (pintype "bidirectional"))
    )
    (net (code "10") (name "FLASH_MOSI") (class "Default")
      (node (ref "MOD1") (pin "4") (pinfunction "PB15/MOSI2_4") (pintype "bidirectional"))
      (node (ref "U4") (pin "5") (pinfunction "SI_5") (pintype "bidirectional"))
    )
    (net (code "11") (name "FLASH_SCK") (class "Default")
      (node (ref "MOD1") (pin "6") (pinfunction "PB13/SCK2_6") (pintype "bidirectional"))
      (node (ref "U4") (pin "6") (pinfunction "SCK_6") (pintype "bidirectional"))
    )
    (net (code "12") (name "GND") (class "Default")
      (node (ref "C1") (pin "2") (pinfunction "P$2_2") (pintype "passive"))
      (node (ref "C10") (pin "2") (pinfunction "P$2_2") (pintype "passive"))
      (node (ref "C11") (pin "2") (pinfunction "P$2_2") (pintype "passive"))
      (node (ref "C12") (pin "2") (pinfunction "P$2_2") (pintype "passive"))
      (node (ref "C13") (pin "2") (pinfunction "P$2_2") (pintype "passive"))
      (node (ref "C14") (pin "2") (pinfunction "P$2_2") (pintype "passive"))
      (node (ref "C15") (pin "2") (pinfunction "P$2_2") (pintype "passive"))
      (node (ref "C16") (pin "2") (pinfunction "P$2_2") (pintype "passive"))
      (node (ref "C17") (pin "-") (pinfunction "-_-") (pintype "passive"))
      (node (ref "C18") (pin "2") (pinfunction "P$2_2") (pintype "passive"))
      (node (ref "C19") (pin "2") (pinfunction "P$2_2") (pintype "passive"))
      (node (ref "C2") (pin "2") (pinfunction "P$2_2") (pintype "passive"))
      (node (ref "C20") (pin "2") (pinfunction "P$2_2") (pintype "passive"))
      (node (ref "C21") (pin "2") (pinfunction "P$2_2") (pintype "passive"))
      (node (ref "C22") (pin "-") (pinfunction "-_-") (pintype "passive"))
      (node (ref "C24") (pin "1") (pinfunction "P$1_1") (pintype "passive"))
      (node (ref "C3") (pin "2") (pinfunction "P$2_2") (pintype "passive"))
      (node (ref "C4") (pin "2") (pinfunction "P$2_2") (pintype "passive"))
      (node (ref "C5") (pin "2") (pinfunction "P$2_2") (pintype "passive"))
      (node (ref "C6") (pin "2") (pinfunction "P$2_2") (pintype "passive"))
      (node (ref "C7") (pin "2") (pinfunction "P$2_2") (pintype "passive"))
      (node (ref "C8") (pin "2") (pinfunction "P$2_2") (pintype "passive"))
      (node (ref "C9") (pin "2") (pinfunction "P$2_2") (pintype "passive"))
      (node (ref "CON1") (pin "GND") (pinfunction "GND_GND") (pintype "bidirectional"))
      (node (ref "CON1") (pin "GND1") (pinfunction "SHEILD_GND1") (pintype "bidirectional"))
      (node (ref "CON1") (pin "GND2") (pinfunction "SHEILD_GND2") (pintype "bidirectional"))
      (node (ref "CON1") (pin "GND3") (pinfunction "SHEILD_GND3") (pintype "bidirectional"))
      (node (ref "CON1") (pin "GND4") (pinfunction "SHEILD_GND4") (pintype "bidirectional"))
      (node (ref "CON2") (pin "5") (pinfunction "GND_5") (pintype "passive"))
      (node (ref "CON3") (pin "5") (pinfunction "GND_5") (pintype "passive"))
      (node (ref "CON5") (pin "4") (pinfunction "GND_4") (pintype "bidirectional"))
      (node (ref "IC1") (pin "4") (pinfunction "GND_4") (pintype "bidirectional"))
      (node (ref "IC2") (pin "1") (pinfunction "OE_1") (pintype "input"))
      (node (ref "IC2") (pin "3") (pinfunction "GND_3") (pintype "power_in"))
      (node (ref "IC3") (pin "1") (pinfunction "OE_1") (pintype "input"))
      (node (ref "IC3") (pin "3") (pinfunction "GND_3") (pintype "power_in"))
      (node (ref "IC4") (pin "1") (pinfunction "OE_1") (pintype "input"))
      (node (ref "IC4") (pin "3") (pinfunction "GND_3") (pintype "power_in"))
      (node (ref "LED4") (pin "C") (pinfunction "C_C") (pintype "passive"))
      (node (ref "LED5") (pin "C") (pinfunction "C_C") (pintype "passive"))
      (node (ref "LED6") (pin "C") (pinfunction "C_C") (pintype "passive"))
      (node (ref "MOD1") (pin "20") (pinfunction "GND_20") (pintype "bidirectional"))
      (node (ref "MOD1") (pin "21") (pinfunction "GND_21") (pintype "bidirectional"))
      (node (ref "MOD2") (pin "1") (pinfunction "GND_1") (pintype "bidirectional"))
      (node (ref "MOD2") (pin "16") (pinfunction "GND_16") (pintype "bidirectional"))
      (node (ref "MOD2") (pin "27") (pinfunction "GND_27") (pintype "bidirectional"))
      (node (ref "MOD2") (pin "39") (pinfunction "GND_39") (pintype "bidirectional"))
      (node (ref "R12") (pin "2") (pinfunction "P$2_2") (pintype "passive"))
      (node (ref "R24") (pin "1") (pinfunction "P$1_1") (pintype "passive"))
      (node (ref "R25") (pin "1") (pinfunction "P$1_1") (pintype "passive"))
      (node (ref "R27") (pin "2") (pinfunction "P$2_2") (pintype "passive"))
      (node (ref "R28") (pin "2") (pinfunction "P$2_2") (pintype "passive"))
      (node (ref "R29") (pin "2") (pinfunction "P$2_2") (pintype "passive"))
      (node (ref "SW1") (pin "P$1") (pinfunction "P_P$1") (pintype "passive"))
      (node (ref "TP4") (pin "TP") (pinfunction "TP_TP") (pintype "input"))
      (node (ref "U1") (pin "2") (pinfunction "GND_2") (pintype "bidirectional"))
      (node (ref "U2") (pin "1") (pinfunction "GND_1") (pintype "bidirectional"))
      (node (ref "U3") (pin "33") (pinfunction "VSS_33") (pintype "passive"))
      (node (ref "U4") (pin "4") (pinfunction "GND_4") (pintype "bidirectional"))
      (node (ref "U5") (pin "4") (pinfunction "GND_4") (pintype "bidirectional"))
      (node (ref "U6") (pin "3") (pinfunction "GND_3") (pintype "power_in"))
      (node (ref "U6") (pin "7") (pinfunction "A0_7") (pintype "input"))
      (node (ref "U6") (pin "8") (pinfunction "A1_8") (pintype "input"))
    )
    (net (code "13") (name "I2C_SDA") (class "Default")
      (node (ref "CON5") (pin "2") (pinfunction "TX/SDA_2") (pintype "bidirectional"))
      (node (ref "IC1") (pin "5") (pinfunction "SDA_5") (pintype "bidirectional"))
      (node (ref "MOD1") (pin "18") (pinfunction "PB9/SDA1_18") (pintype "bidirectional"))
      (node (ref "MOD2") (pin "37") (pinfunction "SIO_26/I2C_SDA_37") (pintype "bidirectional"))
      (node (ref "R15") (pin "1") (pinfunction "P$1_1") (pintype "passive"))
      (node (ref "R19") (pin "2") (pinfunction "P$2_2") (pintype "passive"))
      (node (ref "U6") (pin "6") (pinfunction "SDA_6") (pintype "bidirectional"))
    )
    (net (code "14") (name "IC2_SCL") (class "Default")
      (node (ref "CON5") (pin "1") (pinfunction "RX/SCL_1") (pintype "bidirectional"))
      (node (ref "IC1") (pin "6") (pinfunction "SCL_6") (pintype "bidirectional"))
      (node (ref "MOD1") (pin "17") (pinfunction "PB8/SCL1_17") (pintype "bidirectional"))
      (node (ref "MOD2") (pin "36") (pinfunction "SIO_27/I2C_SCL_36") (pintype "bidirectional"))
      (node (ref "R14") (pin "1") (pinfunction "P$1_1") (pintype "passive"))
      (node (ref "R20") (pin "2") (pinfunction "P$2_2") (pintype "passive"))
      (node (ref "U6") (pin "5") (pinfunction "SCL_5") (pintype "bidirectional"))
    )
    (net (code "15") (name "IF_NRESET") (class "Default")
      (node (ref "C1") (pin "1") (pinfunction "P$1_1") (pintype "passive"))
      (node (ref "CON2") (pin "3") (pinfunction "NRESET_3") (pintype "passive"))
      (node (ref "R1") (pin "1") (pinfunction "P$1_1") (pintype "passive"))
      (node (ref "U3") (pin "2") (pinfunction "~{RESET}/PIO0_0_2") (pintype "bidirectional"))
    )
    (net (code "16") (name "IF_SCL") (class "Default")
      (node (ref "R20") (pin "1") (pinfunction "P$1_1") (pintype "passive"))
      (node (ref "U3") (pin "10") (pinfunction "PIO0_4/SCL_10") (pintype "bidirectional"))
    )
    (net (code "17") (name "IF_SDA") (class "Default")
      (node (ref "R19") (pin "1") (pinfunction "P$1_1") (pintype "passive"))
      (node (ref "U3") (pin "11") (pinfunction "PIO0_5/SDA_11") (pintype "bidirectional"))
    )
    (net (code "18") (name "IF_SWCLK") (class "Default")
      (node (ref "CON2") (pin "4") (pinfunction "SWCLK/TCLK_4") (pintype "passive"))
      (node (ref "U3") (pin "19") (pinfunction "SWCLK/PIO0_10/SCK0/CT16B0_MAT2_19") (pintype "bidirectional"))
    )
    (net (code "19") (name "IF_SWDIO") (class "Default")
      (node (ref "CON2") (pin "2") (pinfunction "SWDIO/TMS_2") (pintype "passive"))
      (node (ref "U3") (pin "25") (pinfunction "SWDIO/PIO0_15/AD4/CT32B1_MAT2_25") (pintype "bidirectional"))
    )
    (net (code "20") (name "LED_COM_GREEN") (class "Default")
      (node (ref "LED2") (pin "C") (pinfunction "C_C") (pintype "passive"))
      (node (ref "U3") (pin "21") (pinfunction "TDI/PIO0_11/AD0/CT32B0_MAT3_21") (pintype "bidirectional"))
    )
    (net (code "21") (name "LED_DAP_BLUE") (class "Default")
      (node (ref "LED1") (pin "C") (pinfunction "C_C") (pintype "passive"))
      (node (ref "U3") (pin "12") (pinfunction "PIO0_21/CT16B1_MAT0/MOSI1_12") (pintype "bidirectional"))
    )
    (net (code "22") (name "LED_PWR_RED") (class "Default")
      (node (ref "LED3") (pin "A") (pinfunction "A_A") (pintype "passive"))
      (node (ref "U3") (pin "7") (pinfunction "PIO0_20/CT16B1_CAP0_7") (pintype "bidirectional"))
    )
    (net (code "23") (name "Net-(C6-P$1)") (class "Default")
      (node (ref "C6") (pin "1") (pinfunction "P$1_1") (pintype "passive"))
      (node (ref "Q1") (pin "P$1") (pinfunction "1_P$1") (pintype "passive"))
      (node (ref "U3") (pin "5") (pinfunction "XTALOUT_5") (pintype "output"))
    )
    (net (code "24") (name "Net-(C7-P$1)") (class "Default")
      (node (ref "C7") (pin "1") (pinfunction "P$1_1") (pintype "passive"))
      (node (ref "Q1") (pin "P$3") (pinfunction "2_P$3") (pintype "passive"))
      (node (ref "U3") (pin "4") (pinfunction "XTALIN_4") (pintype "input"))
    )
    (net (code "25") (name "Net-(C8-P$1)") (class "Default")
      (node (ref "C8") (pin "1") (pinfunction "P$1_1") (pintype "passive"))
      (node (ref "R8") (pin "2") (pinfunction "P$2_2") (pintype "passive"))
      (node (ref "U3") (pin "13") (pinfunction "USB_DM_13") (pintype "bidirectional"))
    )
    (net (code "26") (name "Net-(C9-P$1)") (class "Default")
      (node (ref "C9") (pin "1") (pinfunction "P$1_1") (pintype "passive"))
      (node (ref "R7") (pin "2") (pinfunction "P$2_2") (pintype "passive"))
      (node (ref "R9") (pin "2") (pinfunction "P$2_2") (pintype "passive"))
      (node (ref "U3") (pin "14") (pinfunction "USB_DP_14") (pintype "bidirectional"))
    )
    (net (code "27") (name "Net-(C19-P$1)") (class "Default")
      (node (ref "C19") (pin "1") (pinfunction "P$1_1") (pintype "passive"))
      (node (ref "MOD2") (pin "25") (pinfunction "SIO_00/XL1_25") (pintype "bidirectional"))
      (node (ref "Q2") (pin "X1") (pinfunction "1_X1") (pintype "passive"))
    )
    (net (code "28") (name "Net-(C20-P$1)") (class "Default")
      (node (ref "C20") (pin "1") (pinfunction "P$1_1") (pintype "passive"))
      (node (ref "MOD2") (pin "24") (pinfunction "SIO_01/XL2_24") (pintype "bidirectional"))
      (node (ref "Q2") (pin "X2") (pinfunction "2_X2") (pintype "passive"))
    )
    (net (code "29") (name "Net-(C23-P$1)") (class "Default")
      (node (ref "C23") (pin "1") (pinfunction "P$1_1") (pintype "passive"))
      (node (ref "R18") (pin "1") (pinfunction "P$1_1") (pintype "passive"))
      (node (ref "U6") (pin "1") (pinfunction "VIN+_1") (pintype "input"))
    )
    (net (code "30") (name "Net-(C23-P$2)") (class "Default")
      (node (ref "C23") (pin "2") (pinfunction "P$2_2") (pintype "passive"))
      (node (ref "R17") (pin "1") (pinfunction "P$1_1") (pintype "passive"))
      (node (ref "U6") (pin "2") (pinfunction "VIN-_2") (pintype "input"))
    )
    (net (code "31") (name "Net-(CON1-PadD+)") (class "Default")
      (node (ref "CON1") (pin "D+") (pinfunction "D+_D+") (pintype "bidirectional"))
      (node (ref "U1") (pin "6") (pinfunction "IO1_6") (pintype "bidirectional"))
    )
    (net (code "32") (name "Net-(CON1-PadD-)") (class "Default")
      (node (ref "CON1") (pin "D-") (pinfunction "D-_D-") (pintype "bidirectional"))
      (node (ref "U1") (pin "4") (pinfunction "IO2_4") (pintype "bidirectional"))
    )
    (net (code "33") (name "Net-(IC2A-O)") (class "Default")
      (node (ref "IC2") (pin "4") (pinfunction "O_4") (pintype "tri_state"))
      (node (ref "R21") (pin "1") (pinfunction "P$1_1") (pintype "passive"))
    )
    (net (code "34") (name "Net-(IC3A-O)") (class "Default")
      (node (ref "IC3") (pin "4") (pinfunction "O_4") (pintype "tri_state"))
      (node (ref "R22") (pin "1") (pinfunction "P$1_1") (pintype "passive"))
    )
    (net (code "35") (name "Net-(IC4A-O)") (class "Default")
      (node (ref "IC4") (pin "4") (pinfunction "O_4") (pintype "tri_state"))
      (node (ref "R23") (pin "1") (pinfunction "P$1_1") (pintype "passive"))
    )
    (net (code "36") (name "Net-(MOD2-SIO_09{slash}NFC1)") (class "Default")
      (node (ref "CON4") (pin "RF") (pinfunction "RF_RF") (pintype "bidirectional"))
      (node (ref "MOD2") (pin "15") (pinfunction "SIO_09/NFC1_15") (pintype "bidirectional"))
    )
    (net (code "37") (name "Net-(MOD2-SIO_10{slash}NFC2)") (class "Default")
      (node (ref "CON4") (pin "GND1") (pinfunction "GND_GND1") (pintype "bidirectional"))
      (node (ref "CON4") (pin "GND2") (pinfunction "GND_GND2") (pintype "bidirectional"))
      (node (ref "MOD2") (pin "14") (pinfunction "SIO_10/NFC2_14") (pintype "bidirectional"))
    )
    (net (code "38") (name "Net-(MOD2-SIO_25{slash}SPI_SCK)") (class "Default")
      (node (ref "LED7") (pin "C") (pinfunction "C_C") (pintype "passive"))
      (node (ref "MOD2") (pin "38") (pinfunction "SIO_25/SPI_SCK_38") (pintype "bidirectional"))
    )
    (net (code "39") (name "Net-(R2-P$2)") (class "Default")
      (node (ref "R2") (pin "2") (pinfunction "P$2_2") (pintype "passive"))
      (node (ref "U3") (pin "9") (pinfunction "PIO0_3/USB_VBUS_9") (pintype "bidirectional"))
    )
    (net (code "40") (name "Net-(R5-P$2)") (class "Default")
      (node (ref "D1") (pin "K") (pinfunction "K_K") (pintype "passive"))
      (node (ref "R5") (pin "2") (pinfunction "P$2_2") (pintype "passive"))
      (node (ref "R6") (pin "2") (pinfunction "P$2_2") (pintype "passive"))
      (node (ref "SW1") (pin "P$2") (pinfunction "S_P$2") (pintype "passive"))
    )
    (net (code "41") (name "Net-(R7-P$1)") (class "Default")
      (node (ref "R7") (pin "1") (pinfunction "P$1_1") (pintype "passive"))
      (node (ref "T1") (pin "3") (pinfunction "D_3") (pintype "passive"))
    )
    (net (code "42") (name "Net-(R10-P$1)") (class "Default")
      (node (ref "LED1") (pin "A") (pinfunction "A_A") (pintype "passive"))
      (node (ref "R10") (pin "1") (pinfunction "P$1_1") (pintype "passive"))
    )
    (net (code "43") (name "Net-(R11-P$1)") (class "Default")
      (node (ref "LED2") (pin "A") (pinfunction "A_A") (pintype "passive"))
      (node (ref "R11") (pin "1") (pinfunction "P$1_1") (pintype "passive"))
    )
    (net (code "44") (name "Net-(R12-P$1)") (class "Default")
      (node (ref "LED3") (pin "C") (pinfunction "C_C") (pintype "passive"))
      (node (ref "R12") (pin "1") (pinfunction "P$1_1") (pintype "passive"))
    )
    (net (code "45") (name "Net-(R21-P$2)") (class "Default")
      (node (ref "LED4") (pin "A") (pinfunction "A_A") (pintype "passive"))
      (node (ref "R21") (pin "2") (pinfunction "P$2_2") (pintype "passive"))
    )
    (net (code "46") (name "Net-(R22-P$2)") (class "Default")
      (node (ref "LED5") (pin "A") (pinfunction "A_A") (pintype "passive"))
      (node (ref "R22") (pin "2") (pinfunction "P$2_2") (pintype "passive"))
    )
    (net (code "47") (name "Net-(R23-P$2)") (class "Default")
      (node (ref "LED6") (pin "A") (pinfunction "A_A") (pintype "passive"))
      (node (ref "R23") (pin "2") (pinfunction "P$2_2") (pintype "passive"))
    )
    (net (code "48") (name "Net-(R24-P$2)") (class "Default")
      (node (ref "R24") (pin "2") (pinfunction "P$2_2") (pintype "passive"))
      (node (ref "SW2") (pin "P$2") (pinfunction "S_P$2") (pintype "passive"))
    )
    (net (code "49") (name "Net-(R25-P$2)") (class "Default")
      (node (ref "R25") (pin "2") (pinfunction "P$2_2") (pintype "passive"))
      (node (ref "SW3") (pin "P$2") (pinfunction "S_P$2") (pintype "passive"))
    )
    (net (code "50") (name "Net-(R26-P$1)") (class "Default")
      (node (ref "LED7") (pin "A") (pinfunction "A_A") (pintype "passive"))
      (node (ref "R26") (pin "1") (pinfunction "P$1_1") (pintype "passive"))
    )
    (net (code "51") (name "PA4") (class "Default")
      (node (ref "IC2") (pin "2") (pinfunction "I_2") (pintype "input"))
      (node (ref "MOD1") (pin "38") (pinfunction "PA4/ADC1.4_38") (pintype "bidirectional"))
      (node (ref "R27") (pin "1") (pinfunction "P$1_1") (pintype "passive"))
    )
    (net (code "52") (name "PA5") (class "Default")
      (node (ref "IC3") (pin "2") (pinfunction "I_2") (pintype "input"))
      (node (ref "MOD1") (pin "34") (pinfunction "PA5/ADC1.5_34") (pintype "bidirectional"))
      (node (ref "R28") (pin "1") (pinfunction "P$1_1") (pintype "passive"))
    )
    (net (code "53") (name "PB0") (class "Default")
      (node (ref "IC4") (pin "2") (pinfunction "I_2") (pintype "input"))
      (node (ref "MOD1") (pin "37") (pinfunction "PB0/ADC1.8_37") (pintype "bidirectional"))
      (node (ref "R29") (pin "1") (pinfunction "P$1_1") (pintype "passive"))
    )
    (net (code "54") (name "PB4") (class "Default")
      (node (ref "MOD1") (pin "16") (pinfunction "PC13_16") (pintype "bidirectional"))
      (node (ref "SW3") (pin "P$1") (pinfunction "P_P$1") (pintype "passive"))
    )
    (net (code "55") (name "PB10") (class "Default")
      (node (ref "MOD1") (pin "19") (pinfunction "PB10_19") (pintype "bidirectional"))
      (node (ref "SW2") (pin "P$1") (pinfunction "P_P$1") (pintype "passive"))
    )
    (net (code "56") (name "PIO0_12") (class "Default")
      (node (ref "U3") (pin "22") (pinfunction "TMS/PIO0_12/AD1/CT32B1_CAP0_22") (pintype "bidirectional"))
    )
    (net (code "57") (name "PIO0_14") (class "Default")
      (node (ref "U3") (pin "24") (pinfunction "~{TRST}/PIO0_14/AD3/CT32B1_MAT1_24") (pintype "bidirectional"))
    )
    (net (code "58") (name "PIO0_15") (class "Default")
      (node (ref "U3") (pin "28") (pinfunction "PIO1_15/~{DCD}/CT16B0_MAT2/SCK1_28") (pintype "bidirectional"))
    )
    (net (code "59") (name "PIO0_16") (class "Default")
      (node (ref "U3") (pin "26") (pinfunction "PIO0_16/AD5/CT32B1_MAT3/WAKEUP_26") (pintype "bidirectional"))
    )
    (net (code "60") (name "PIO0_22") (class "Default")
      (node (ref "U3") (pin "20") (pinfunction "PIO0_22/AD6/CT16B1_MAT1/MISO1_20") (pintype "bidirectional"))
    )
    (net (code "61") (name "PIO0_23") (class "Default")
      (node (ref "U3") (pin "27") (pinfunction "PIO0_23/AD7_27") (pintype "bidirectional"))
    )
    (net (code "62") (name "PIO_13") (class "Default")
      (node (ref "U3") (pin "23") (pinfunction "TDO/PIO0_13/AD2/CT32B1_MAT0_23") (pintype "bidirectional"))
    )
    (net (code "63") (name "SFLASH_CS") (class "Default")
      (node (ref "MOD2") (pin "12") (pinfunction "SIO_12/SFLASH_CS_12") (pintype "bidirectional"))
      (node (ref "U5") (pin "1") (pinfunction "~{CS}_1") (pintype "bidirectional"))
    )
    (net (code "64") (name "SFLASH_MISO") (class "Default")
      (node (ref "MOD2") (pin "11") (pinfunction "SIO_14/SFLASH_MISO_11") (pintype "bidirectional"))
      (node (ref "U5") (pin "2") (pinfunction "SO_2") (pintype "bidirectional"))
    )
    (net (code "65") (name "SFLASH_MOSI") (class "Default")
      (node (ref "MOD2") (pin "8") (pinfunction "SIO_20/SFLASH_MOSI_8") (pintype "bidirectional"))
      (node (ref "U5") (pin "5") (pinfunction "SI_5") (pintype "bidirectional"))
    )
    (net (code "66") (name "SFLASH_SCK") (class "Default")
      (node (ref "MOD2") (pin "10") (pinfunction "SIO_16/SFLASH_SCK_10") (pintype "bidirectional"))
      (node (ref "U5") (pin "6") (pinfunction "SCK_6") (pintype "bidirectional"))
    )
    (net (code "67") (name "TGT_CTS") (class "Default")
      (node (ref "U3") (pin "30") (pinfunction "PIO0_17/~{RTS}/CT32B0_CAP0/SCLK_30") (pintype "bidirectional"))
    )
    (net (code "68") (name "TGT_NRESET") (class "Default")
      (node (ref "D1") (pin "A") (pinfunction "A_A") (pintype "passive"))
      (node (ref "JP4") (pin "2") (pinfunction "2_2") (pintype "passive"))
      (node (ref "U3") (pin "8") (pinfunction "PIO0_2/SSEL0/CT16B0_CAP0_8") (pintype "bidirectional"))
    )
    (net (code "69") (name "TGT_NRESET_BL652") (class "Default")
      (node (ref "C16") (pin "1") (pinfunction "P$1_1") (pintype "passive"))
      (node (ref "CON3") (pin "3") (pinfunction "NRESET_3") (pintype "passive"))
      (node (ref "JP4") (pin "3") (pinfunction "3_3") (pintype "passive"))
      (node (ref "MOD2") (pin "7") (pinfunction "~{RESET}_7") (pintype "bidirectional"))
      (node (ref "R16") (pin "1") (pinfunction "P$1_1") (pintype "passive"))
    )
    (net (code "70") (name "TGT_NRESET_EMW3166") (class "Default")
      (node (ref "C11") (pin "1") (pinfunction "P$1_1") (pintype "passive"))
      (node (ref "JP4") (pin "1") (pinfunction "1_1") (pintype "passive"))
      (node (ref "MOD1") (pin "13") (pinfunction "~{RESET}_13") (pintype "bidirectional"))
      (node (ref "R13") (pin "1") (pinfunction "P$1_1") (pintype "passive"))
    )
    (net (code "71") (name "TGT_NRESET_FB") (class "Default")
      (node (ref "R5") (pin "1") (pinfunction "P$1_1") (pintype "passive"))
      (node (ref "U3") (pin "3") (pinfunction "PIO0_1/CLKOUT/CT32B0_MAT2/USB_FTOGGLE_3") (pintype "bidirectional"))
    )
    (net (code "72") (name "TGT_NRESET_FB_ISP") (class "Default")
      (node (ref "R6") (pin "1") (pinfunction "P$1_1") (pintype "passive"))
      (node (ref "U3") (pin "1") (pinfunction "PIO1_19/~{DTR}/SSEL1_1") (pintype "bidirectional"))
    )
    (net (code "73") (name "TGT_NRST_BL652_GPIO") (class "Default")
      (node (ref "JP4") (pin "4") (pinfunction "4_4") (pintype "passive"))
      (node (ref "MOD1") (pin "33") (pinfunction "PA10_33") (pintype "bidirectional"))
    )
    (net (code "74") (name "TGT_RTS") (class "Default")
      (node (ref "R4") (pin "2") (pinfunction "P$2_2") (pintype "passive"))
      (node (ref "U3") (pin "16") (pinfunction "PIO0_7/~{CTS}_16") (pintype "bidirectional"))
    )
    (net (code "75") (name "TGT_RX") (class "Default")
      (node (ref "MOD1") (pin "12") (pinfunction "PC7/RX6_12") (pintype "bidirectional"))
      (node (ref "U3") (pin "32") (pinfunction "PIO0_19/TXD/CT32B0_MAT1_32") (pintype "bidirectional"))
    )
    (net (code "76") (name "TGT_SWCLK") (class "Default")
      (node (ref "JP6") (pin "2") (pinfunction "2_2") (pintype "passive"))
      (node (ref "R4") (pin "1") (pinfunction "P$1_1") (pintype "passive"))
      (node (ref "U3") (pin "18") (pinfunction "PIO0_9/MOSI0/CT16B0_MAT1_18") (pintype "bidirectional"))
    )
    (net (code "77") (name "TGT_SWCLK_BL652") (class "Default")
      (node (ref "CON3") (pin "4") (pinfunction "SWCLK/TCLK_4") (pintype "passive"))
      (node (ref "JP6") (pin "3") (pinfunction "3_3") (pintype "passive"))
      (node (ref "MOD2") (pin "6") (pinfunction "SWDCLK_6") (pintype "bidirectional"))
    )
    (net (code "78") (name "TGT_SWCLK_BL652_GPIO") (class "Default")
      (node (ref "JP6") (pin "4") (pinfunction "4_4") (pintype "passive"))
      (node (ref "MOD1") (pin "27") (pinfunction "PB3_27") (pintype "bidirectional"))
    )
    (net (code "79") (name "TGT_SWCLK_EMW3166") (class "Default")
      (node (ref "JP6") (pin "1") (pinfunction "1_1") (pintype "passive"))
      (node (ref "MOD1") (pin "25") (pinfunction "PA14/SWCLK_25") (pintype "bidirectional"))
    )
    (net (code "80") (name "TGT_SWDIO") (class "Default")
      (node (ref "JP5") (pin "2") (pinfunction "2_2") (pintype "passive"))
      (node (ref "U3") (pin "17") (pinfunction "PIO0_8/MISO0/CT16B0_MAT0_17") (pintype "bidirectional"))
    )
    (net (code "81") (name "TGT_SWDIO_BL652") (class "Default")
      (node (ref "CON3") (pin "2") (pinfunction "SWDIO/TMS_2") (pintype "passive"))
      (node (ref "JP5") (pin "3") (pinfunction "3_3") (pintype "passive"))
      (node (ref "MOD2") (pin "5") (pinfunction "SWDIO_5") (pintype "bidirectional"))
    )
    (net (code "82") (name "TGT_SWDIO_BL652_GPIO") (class "Default")
      (node (ref "JP5") (pin "4") (pinfunction "4_4") (pintype "passive"))
      (node (ref "MOD1") (pin "31") (pinfunction "PB4_31") (pintype "bidirectional"))
    )
    (net (code "83") (name "TGT_SWDIO_EMW3166") (class "Default")
      (node (ref "JP5") (pin "1") (pinfunction "1_1") (pintype "passive"))
      (node (ref "MOD1") (pin "26") (pinfunction "PA13/SWDIO_26") (pintype "bidirectional"))
    )
    (net (code "84") (name "TGT_TX") (class "Default")
      (node (ref "MOD1") (pin "8") (pinfunction "PC6/TX6_8") (pintype "bidirectional"))
      (node (ref "U3") (pin "31") (pinfunction "PIO0_18/RXD/CT32B0_MAT0_31") (pintype "bidirectional"))
    )
    (net (code "85") (name "USB-D+") (class "Default")
      (node (ref "R9") (pin "1") (pinfunction "P$1_1") (pintype "passive"))
      (node (ref "U1") (pin "1") (pinfunction "IO1_1") (pintype "bidirectional"))
    )
    (net (code "86") (name "USB-D-") (class "Default")
      (node (ref "R8") (pin "1") (pinfunction "P$1_1") (pintype "passive"))
      (node (ref "U1") (pin "3") (pinfunction "IO2_3") (pintype "bidirectional"))
    )
    (net (code "87") (name "USB-SCON") (class "Default")
      (node (ref "T1") (pin "1") (pinfunction "G_1") (pintype "passive"))
      (node (ref "U3") (pin "15") (pinfunction "PIO0_6/~{USB_CONNECT}/SCK0_15") (pintype "bidirectional"))
    )
    (net (code "88") (name "unconnected-(CON2-SWO{slash}TDO-Pad6)") (class "Default")
      (node (ref "CON2") (pin "6") (pinfunction "SWO/TDO_6") (pintype "passive"))
    )
    (net (code "89") (name "unconnected-(CON3-SWO{slash}TDO-Pad6)") (class "Default")
      (node (ref "CON3") (pin "6") (pinfunction "SWO/TDO_6") (pintype "passive"))
    )
    (net (code "90") (name "unconnected-(IC1-NC1-Pad1)") (class "Default")
      (node (ref "IC1") (pin "1") (pinfunction "NC1_1") (pintype "bidirectional"))
    )
    (net (code "91") (name "unconnected-(IC1-NC2-Pad2)") (class "Default")
      (node (ref "IC1") (pin "2") (pinfunction "NC2_2") (pintype "bidirectional"))
    )
    (net (code "92") (name "unconnected-(IC1-NC3-Pad3)") (class "Default")
      (node (ref "IC1") (pin "3") (pinfunction "NC3_3") (pintype "bidirectional"))
    )
    (net (code "93") (name "unconnected-(IC1-NC7-Pad7)") (class "Default")
      (node (ref "IC1") (pin "7") (pinfunction "NC7_7") (pintype "bidirectional"))
    )
    (net (code "94") (name "unconnected-(MOD1-ANT-Pad41)") (class "Default")
      (node (ref "MOD1") (pin "41") (pinfunction "ANT_41") (pintype "bidirectional"))
    )
    (net (code "95") (name "unconnected-(MOD1-PB2-Pad2)") (class "Default")
      (node (ref "MOD1") (pin "2") (pinfunction "PB2_2") (pintype "bidirectional"))
    )
    (net (code "96") (name "unconnected-(MOD1-PB12{slash}NSS2-Pad5)") (class "Default")
      (node (ref "MOD1") (pin "5") (pinfunction "PB12/NSS2_5") (pintype "bidirectional"))
    )
    (net (code "97") (name "unconnected-(MOD1-PC0-Pad14)") (class "Default")
      (node (ref "MOD1") (pin "14") (pinfunction "PC0_14") (pintype "bidirectional"))
    )
    (net (code "98") (name "unconnected-(MOD2-SIO_02{slash}AIN0-Pad23)") (class "Default")
      (node (ref "MOD2") (pin "23") (pinfunction "SIO_02/AIN0_23") (pintype "bidirectional"))
    )
    (net (code "99") (name "unconnected-(MOD2-SIO_03{slash}AIN1-Pad22)") (class "Default")
      (node (ref "MOD2") (pin "22") (pinfunction "SIO_03/AIN1_22") (pintype "bidirectional"))
    )
    (net (code "100") (name "unconnected-(MOD2-SIO_04{slash}AIN2-Pad21)") (class "Default")
      (node (ref "MOD2") (pin "21") (pinfunction "SIO_04/AIN2_21") (pintype "bidirectional"))
    )
    (net (code "101") (name "unconnected-(MOD2-SIO_11-Pad13)") (class "Default")
      (node (ref "MOD2") (pin "13") (pinfunction "SIO_11_13") (pintype "bidirectional"))
    )
    (net (code "102") (name "unconnected-(MOD2-SIO_13{slash}~{AUTORUN}-Pad28)") (class "Default")
      (node (ref "MOD2") (pin "28") (pinfunction "SIO_13/~{AUTORUN}_28") (pintype "bidirectional"))
    )
    (net (code "103") (name "unconnected-(MOD2-SIO_15-Pad29)") (class "Default")
      (node (ref "MOD2") (pin "29") (pinfunction "SIO_15_29") (pintype "bidirectional"))
    )
    (net (code "104") (name "unconnected-(MOD2-SIO_17-Pad30)") (class "Default")
      (node (ref "MOD2") (pin "30") (pinfunction "SIO_17_30") (pintype "bidirectional"))
    )
    (net (code "105") (name "unconnected-(MOD2-SIO_18-Pad9)") (class "Default")
      (node (ref "MOD2") (pin "9") (pinfunction "SIO_18_9") (pintype "bidirectional"))
    )
    (net (code "106") (name "unconnected-(MOD2-SIO_19-Pad31)") (class "Default")
      (node (ref "MOD2") (pin "31") (pinfunction "SIO_19_31") (pintype "bidirectional"))
    )
    (net (code "107") (name "unconnected-(MOD2-SIO_22-Pad4)") (class "Default")
      (node (ref "MOD2") (pin "4") (pinfunction "SIO_22_4") (pintype "bidirectional"))
    )
    (net (code "108") (name "unconnected-(MOD2-SIO_23{slash}SPI_MOSI-Pad3)") (class "Default")
      (node (ref "MOD2") (pin "3") (pinfunction "SIO_23/SPI_MOSI_3") (pintype "bidirectional"))
    )
    (net (code "109") (name "unconnected-(MOD2-SIO_24{slash}SPI_MISO-Pad2)") (class "Default")
      (node (ref "MOD2") (pin "2") (pinfunction "SIO_24/SPI_MISO_2") (pintype "bidirectional"))
    )
    (net (code "110") (name "unconnected-(MOD2-SIO_28{slash}AIN4-Pad35)") (class "Default")
      (node (ref "MOD2") (pin "35") (pinfunction "SIO_28/AIN4_35") (pintype "bidirectional"))
    )
    (net (code "111") (name "unconnected-(MOD2-SIO_29{slash}AIN5-Pad34)") (class "Default")
      (node (ref "MOD2") (pin "34") (pinfunction "SIO_29/AIN5_34") (pintype "bidirectional"))
    )
    (net (code "112") (name "unconnected-(MOD2-SIO_30{slash}AIN6-Pad33)") (class "Default")
      (node (ref "MOD2") (pin "33") (pinfunction "SIO_30/AIN6_33") (pintype "bidirectional"))
    )
    (net (code "113") (name "unconnected-(MOD2-SIO_31{slash}AIN7-Pad32)") (class "Default")
      (node (ref "MOD2") (pin "32") (pinfunction "SIO_31/AIN7_32") (pintype "bidirectional"))
    )
  )
)
